# Menorah.net
KiCad netlist of a schematic drawn in EAGLE
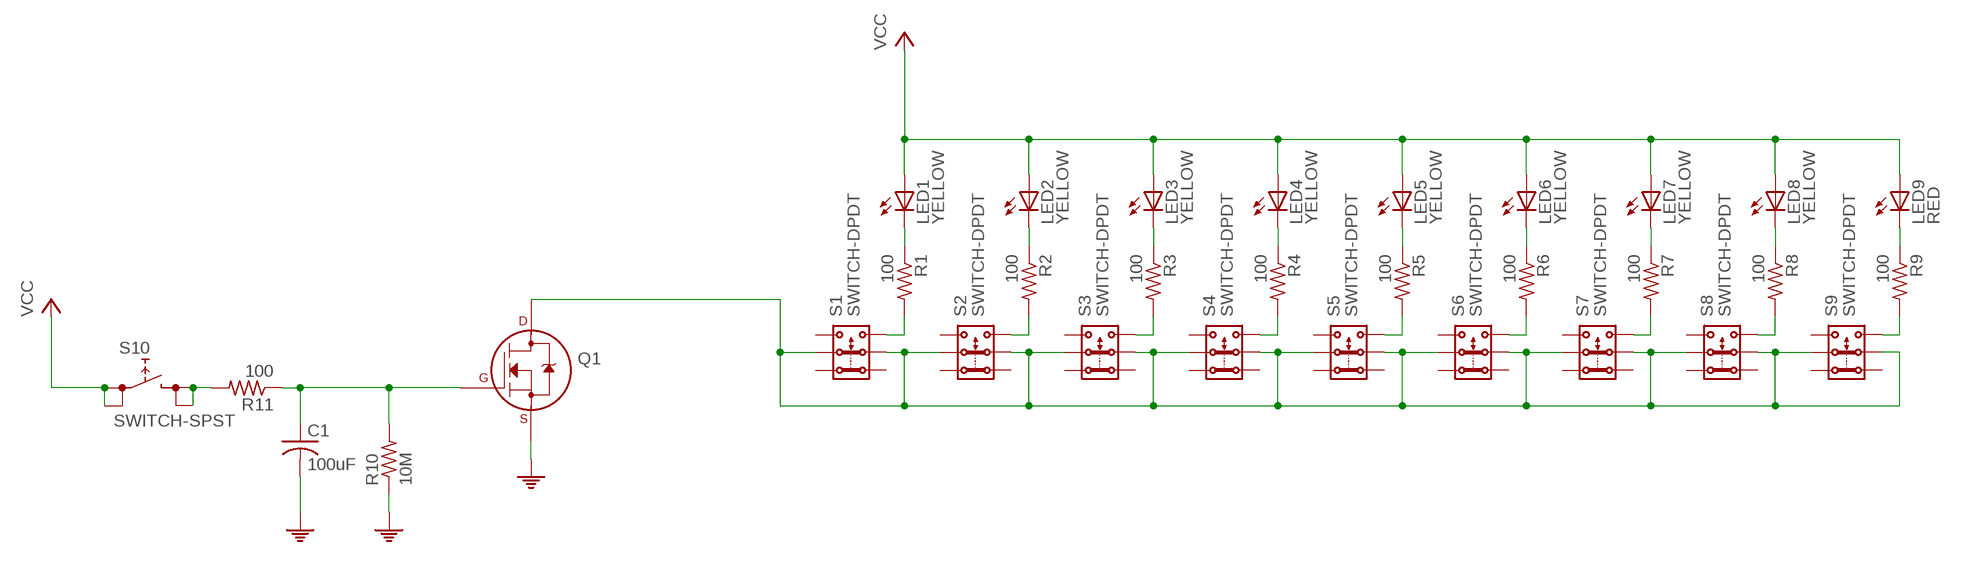
[diagram p0: schematic, sheet 1]

(export (version "E")
  (design (tool "Eeschema 10.0.6"))
  (components
    (comp (ref "C1")
      (value "100uF")
      (footprint "eagle-import:C1206")
      (libsource (lib "eagle-import") (part "C-USC1206"))
    )
    (comp (ref "LED1")
      (value "YELLOW")
      (footprint "eagle-import:CHIPLED_0805")
      (libsource (lib "eagle-import") (part "LEDCHIPLED_0805"))
    )
    (comp (ref "LED2")
      (value "YELLOW")
      (footprint "eagle-import:CHIPLED_0805")
      (libsource (lib "eagle-import") (part "LEDCHIPLED_0805"))
    )
    (comp (ref "LED3")
      (value "YELLOW")
      (footprint "eagle-import:CHIPLED_0805")
      (libsource (lib "eagle-import") (part "LEDCHIPLED_0805"))
    )
    (comp (ref "LED4")
      (value "YELLOW")
      (footprint "eagle-import:CHIPLED_0805")
      (libsource (lib "eagle-import") (part "LEDCHIPLED_0805"))
    )
    (comp (ref "LED5")
      (value "YELLOW")
      (footprint "eagle-import:CHIPLED_0805")
      (libsource (lib "eagle-import") (part "LEDCHIPLED_0805"))
    )
    (comp (ref "LED6")
      (value "YELLOW")
      (footprint "eagle-import:CHIPLED_0805")
      (libsource (lib "eagle-import") (part "LEDCHIPLED_0805"))
    )
    (comp (ref "LED7")
      (value "YELLOW")
      (footprint "eagle-import:CHIPLED_0805")
      (libsource (lib "eagle-import") (part "LEDCHIPLED_0805"))
    )
    (comp (ref "LED8")
      (value "YELLOW")
      (footprint "eagle-import:CHIPLED_0805")
      (libsource (lib "eagle-import") (part "LEDCHIPLED_0805"))
    )
    (comp (ref "LED9")
      (value "RED")
      (footprint "eagle-import:CHIPLED_0805")
      (libsource (lib "eagle-import") (part "LEDCHIPLED_0805"))
    )
    (comp (ref "Q1")
      (value "2N7002A_SOT23")
      (footprint "eagle-import:SOT-23")
      (libsource (lib "eagle-import") (part "2N700_SOT232A"))
    )
    (comp (ref "R1")
      (value "100")
      (footprint "eagle-import:R0805")
      (libsource (lib "eagle-import") (part "R-US_R0805"))
    )
    (comp (ref "R2")
      (value "100")
      (footprint "eagle-import:R0805")
      (libsource (lib "eagle-import") (part "R-US_R0805"))
    )
    (comp (ref "R3")
      (value "100")
      (footprint "eagle-import:R0805")
      (libsource (lib "eagle-import") (part "R-US_R0805"))
    )
    (comp (ref "R4")
      (value "100")
      (footprint "eagle-import:R0805")
      (libsource (lib "eagle-import") (part "R-US_R0805"))
    )
    (comp (ref "R5")
      (value "100")
      (footprint "eagle-import:R0805")
      (libsource (lib "eagle-import") (part "R-US_R0805"))
    )
    (comp (ref "R6")
      (value "100")
      (footprint "eagle-import:R0805")
      (libsource (lib "eagle-import") (part "R-US_R0805"))
    )
    (comp (ref "R7")
      (value "100")
      (footprint "eagle-import:R0805")
      (libsource (lib "eagle-import") (part "R-US_R0805"))
    )
    (comp (ref "R8")
      (value "100")
      (footprint "eagle-import:R0805")
      (libsource (lib "eagle-import") (part "R-US_R0805"))
    )
    (comp (ref "R9")
      (value "100")
      (footprint "eagle-import:R0805")
      (libsource (lib "eagle-import") (part "R-US_R0805"))
    )
    (comp (ref "R10")
      (value "10M")
      (footprint "eagle-import:R0805")
      (libsource (lib "eagle-import") (part "R-US_R0805"))
    )
    (comp (ref "R11")
      (value "100")
      (footprint "eagle-import:R0805")
      (libsource (lib "eagle-import") (part "R-US_R0805"))
    )
    (comp (ref "S1")
      (value "SWITCH-DPDT")
      (footprint "eagle-import:JS202011SCQN")
      (libsource (lib "eagle-import") (part "SWITCH-DPDT"))
    )
    (comp (ref "S2")
      (value "SWITCH-DPDT")
      (footprint "eagle-import:JS202011SCQN")
      (libsource (lib "eagle-import") (part "SWITCH-DPDT"))
    )
    (comp (ref "S3")
      (value "SWITCH-DPDT")
      (footprint "eagle-import:JS202011SCQN")
      (libsource (lib "eagle-import") (part "SWITCH-DPDT"))
    )
    (comp (ref "S4")
      (value "SWITCH-DPDT")
      (footprint "eagle-import:JS202011SCQN")
      (libsource (lib "eagle-import") (part "SWITCH-DPDT"))
    )
    (comp (ref "S5")
      (value "SWITCH-DPDT")
      (footprint "eagle-import:JS202011SCQN")
      (libsource (lib "eagle-import") (part "SWITCH-DPDT"))
    )
    (comp (ref "S6")
      (value "SWITCH-DPDT")
      (footprint "eagle-import:JS202011SCQN")
      (libsource (lib "eagle-import") (part "SWITCH-DPDT"))
    )
    (comp (ref "S7")
      (value "SWITCH-DPDT")
      (footprint "eagle-import:JS202011SCQN")
      (libsource (lib "eagle-import") (part "SWITCH-DPDT"))
    )
    (comp (ref "S8")
      (value "SWITCH-DPDT")
      (footprint "eagle-import:JS202011SCQN")
      (libsource (lib "eagle-import") (part "SWITCH-DPDT"))
    )
    (comp (ref "S9")
      (value "SWITCH-DPDT")
      (footprint "eagle-import:JS202011SCQN")
      (libsource (lib "eagle-import") (part "SWITCH-DPDT"))
    )
    (comp (ref "S10")
      (value "SWITCH-SPST")
      (footprint "eagle-import:KS-01Q-01")
      (libsource (lib "eagle-import") (part "SWITCH-SPST"))
    )
  )
  (nets
    (net (code "1") (name "Net-(LED1-PadC)") (class "Default")
      (node (ref "LED1") (pin "C") (pinfunction "C_C") (pintype "passive"))
      (node (ref "R1") (pin "1") (pinfunction "1_1") (pintype "passive"))
    )
    (net (code "2") (name "Net-(LED2-PadC)") (class "Default")
      (node (ref "LED2") (pin "C") (pinfunction "C_C") (pintype "passive"))
      (node (ref "R2") (pin "1") (pinfunction "1_1") (pintype "passive"))
    )
    (net (code "3") (name "Net-(LED3-PadC)") (class "Default")
      (node (ref "LED3") (pin "C") (pinfunction "C_C") (pintype "passive"))
      (node (ref "R3") (pin "1") (pinfunction "1_1") (pintype "passive"))
    )
    (net (code "4") (name "Net-(LED4-PadC)") (class "Default")
      (node (ref "LED4") (pin "C") (pinfunction "C_C") (pintype "passive"))
      (node (ref "R4") (pin "1") (pinfunction "1_1") (pintype "passive"))
    )
    (net (code "5") (name "Net-(LED5-PadC)") (class "Default")
      (node (ref "LED5") (pin "C") (pinfunction "C_C") (pintype "passive"))
      (node (ref "R5") (pin "1") (pinfunction "1_1") (pintype "passive"))
    )
    (net (code "6") (name "Net-(LED6-PadC)") (class "Default")
      (node (ref "LED6") (pin "C") (pinfunction "C_C") (pintype "passive"))
      (node (ref "R6") (pin "1") (pinfunction "1_1") (pintype "passive"))
    )
    (net (code "7") (name "Net-(LED7-PadC)") (class "Default")
      (node (ref "LED7") (pin "C") (pinfunction "C_C") (pintype "passive"))
      (node (ref "R7") (pin "1") (pinfunction "1_1") (pintype "passive"))
    )
    (net (code "8") (name "Net-(LED8-PadC)") (class "Default")
      (node (ref "LED8") (pin "C") (pinfunction "C_C") (pintype "passive"))
      (node (ref "R8") (pin "1") (pinfunction "1_1") (pintype "passive"))
    )
    (net (code "9") (name "Net-(LED9-PadC)") (class "Default")
      (node (ref "LED9") (pin "C") (pinfunction "C_C") (pintype "passive"))
      (node (ref "R9") (pin "1") (pinfunction "1_1") (pintype "passive"))
    )
    (net (code "10") (name "Net-(Q1-D)") (class "Default")
      (node (ref "Q1") (pin "3") (pinfunction "D_3") (pintype "bidirectional"))
      (node (ref "S1") (pin "2") (pinfunction "2_2") (pintype "passive"))
      (node (ref "S1") (pin "5") (pinfunction "5_5") (pintype "passive"))
      (node (ref "S2") (pin "2") (pinfunction "2_2") (pintype "passive"))
      (node (ref "S2") (pin "5") (pinfunction "5_5") (pintype "passive"))
      (node (ref "S3") (pin "2") (pinfunction "2_2") (pintype "passive"))
      (node (ref "S3") (pin "5") (pinfunction "5_5") (pintype "passive"))
      (node (ref "S4") (pin "2") (pinfunction "2_2") (pintype "passive"))
      (node (ref "S4") (pin "5") (pinfunction "5_5") (pintype "passive"))
      (node (ref "S5") (pin "2") (pinfunction "2_2") (pintype "passive"))
      (node (ref "S5") (pin "5") (pinfunction "5_5") (pintype "passive"))
      (node (ref "S6") (pin "2") (pinfunction "2_2") (pintype "passive"))
      (node (ref "S6") (pin "5") (pinfunction "5_5") (pintype "passive"))
      (node (ref "S7") (pin "2") (pinfunction "2_2") (pintype "passive"))
      (node (ref "S7") (pin "5") (pinfunction "5_5") (pintype "passive"))
      (node (ref "S8") (pin "2") (pinfunction "2_2") (pintype "passive"))
      (node (ref "S8") (pin "5") (pinfunction "5_5") (pintype "passive"))
      (node (ref "S9") (pin "2") (pinfunction "2_2") (pintype "passive"))
      (node (ref "S9") (pin "5") (pinfunction "5_5") (pintype "passive"))
    )
    (net (code "11") (name "Net-(Q1-G)") (class "Default")
      (node (ref "C1") (pin "1") (pinfunction "1_1") (pintype "passive"))
      (node (ref "Q1") (pin "1") (pinfunction "G_1") (pintype "tri_state"))
      (node (ref "R10") (pin "2") (pinfunction "2_2") (pintype "passive"))
      (node (ref "R11") (pin "1") (pinfunction "1_1") (pintype "passive"))
    )
    (net (code "12") (name "Net-(R1-Pad2)") (class "Default")
      (node (ref "R1") (pin "2") (pinfunction "2_2") (pintype "passive"))
      (node (ref "S1") (pin "3") (pinfunction "3_3") (pintype "passive"))
    )
    (net (code "13") (name "Net-(R2-Pad2)") (class "Default")
      (node (ref "R2") (pin "2") (pinfunction "2_2") (pintype "passive"))
      (node (ref "S2") (pin "3") (pinfunction "3_3") (pintype "passive"))
    )
    (net (code "14") (name "Net-(R3-Pad2)") (class "Default")
      (node (ref "R3") (pin "2") (pinfunction "2_2") (pintype "passive"))
      (node (ref "S3") (pin "3") (pinfunction "3_3") (pintype "passive"))
    )
    (net (code "15") (name "Net-(R4-Pad2)") (class "Default")
      (node (ref "R4") (pin "2") (pinfunction "2_2") (pintype "passive"))
      (node (ref "S4") (pin "3") (pinfunction "3_3") (pintype "passive"))
    )
    (net (code "16") (name "Net-(R5-Pad2)") (class "Default")
      (node (ref "R5") (pin "2") (pinfunction "2_2") (pintype "passive"))
      (node (ref "S5") (pin "3") (pinfunction "3_3") (pintype "passive"))
    )
    (net (code "17") (name "Net-(R6-Pad2)") (class "Default")
      (node (ref "R6") (pin "2") (pinfunction "2_2") (pintype "passive"))
      (node (ref "S6") (pin "3") (pinfunction "3_3") (pintype "passive"))
    )
    (net (code "18") (name "Net-(R7-Pad2)") (class "Default")
      (node (ref "R7") (pin "2") (pinfunction "2_2") (pintype "passive"))
      (node (ref "S7") (pin "3") (pinfunction "3_3") (pintype "passive"))
    )
    (net (code "19") (name "Net-(R8-Pad2)") (class "Default")
      (node (ref "R8") (pin "2") (pinfunction "2_2") (pintype "passive"))
      (node (ref "S8") (pin "3") (pinfunction "3_3") (pintype "passive"))
    )
    (net (code "20") (name "Net-(R9-Pad2)") (class "Default")
      (node (ref "R9") (pin "2") (pinfunction "2_2") (pintype "passive"))
      (node (ref "S9") (pin "3") (pinfunction "3_3") (pintype "passive"))
    )
    (net (code "21") (name "Net-(R11-Pad2)") (class "Default")
      (node (ref "R11") (pin "2") (pinfunction "2_2") (pintype "passive"))
      (node (ref "S10") (pin "2") (pinfunction "1_2") (pintype "passive"))
      (node (ref "S10") (pin "4") (pinfunction "1_4") (pintype "passive"))
    )
    (net (code "22") (name "PE") (class "Default")
      (node (ref "C1") (pin "2") (pinfunction "2_2") (pintype "passive"))
      (node (ref "Q1") (pin "2") (pinfunction "S_2") (pintype "bidirectional"))
      (node (ref "R10") (pin "1") (pinfunction "1_1") (pintype "passive"))
    )
    (net (code "23") (name "VCC") (class "Default")
      (node (ref "LED1") (pin "A") (pinfunction "A_A") (pintype "passive"))
      (node (ref "LED2") (pin "A") (pinfunction "A_A") (pintype "passive"))
      (node (ref "LED3") (pin "A") (pinfunction "A_A") (pintype "passive"))
      (node (ref "LED4") (pin "A") (pinfunction "A_A") (pintype "passive"))
      (node (ref "LED5") (pin "A") (pinfunction "A_A") (pintype "passive"))
      (node (ref "LED6") (pin "A") (pinfunction "A_A") (pintype "passive"))
      (node (ref "LED7") (pin "A") (pinfunction "A_A") (pintype "passive"))
      (node (ref "LED8") (pin "A") (pinfunction "A_A") (pintype "passive"))
      (node (ref "LED9") (pin "A") (pinfunction "A_A") (pintype "passive"))
      (node (ref "S10") (pin "1") (pinfunction "0_1") (pintype "passive"))
      (node (ref "S10") (pin "3") (pinfunction "0_3") (pintype "passive"))
    )
    (net (code "24") (name "unconnected-(S1-Pad1)") (class "Default")
      (node (ref "S1") (pin "1") (pinfunction "1_1") (pintype "passive"))
    )
    (net (code "25") (name "unconnected-(S1-Pad4)") (class "Default")
      (node (ref "S1") (pin "4") (pinfunction "4_4") (pintype "passive"))
    )
    (net (code "26") (name "unconnected-(S1-Pad6)") (class "Default")
      (node (ref "S1") (pin "6") (pinfunction "6_6") (pintype "passive"))
    )
    (net (code "27") (name "unconnected-(S2-Pad1)") (class "Default")
      (node (ref "S2") (pin "1") (pinfunction "1_1") (pintype "passive"))
    )
    (net (code "28") (name "unconnected-(S2-Pad4)") (class "Default")
      (node (ref "S2") (pin "4") (pinfunction "4_4") (pintype "passive"))
    )
    (net (code "29") (name "unconnected-(S2-Pad6)") (class "Default")
      (node (ref "S2") (pin "6") (pinfunction "6_6") (pintype "passive"))
    )
    (net (code "30") (name "unconnected-(S3-Pad1)") (class "Default")
      (node (ref "S3") (pin "1") (pinfunction "1_1") (pintype "passive"))
    )
    (net (code "31") (name "unconnected-(S3-Pad4)") (class "Default")
      (node (ref "S3") (pin "4") (pinfunction "4_4") (pintype "passive"))
    )
    (net (code "32") (name "unconnected-(S3-Pad6)") (class "Default")
      (node (ref "S3") (pin "6") (pinfunction "6_6") (pintype "passive"))
    )
    (net (code "33") (name "unconnected-(S4-Pad1)") (class "Default")
      (node (ref "S4") (pin "1") (pinfunction "1_1") (pintype "passive"))
    )
    (net (code "34") (name "unconnected-(S4-Pad4)") (class "Default")
      (node (ref "S4") (pin "4") (pinfunction "4_4") (pintype "passive"))
    )
    (net (code "35") (name "unconnected-(S4-Pad6)") (class "Default")
      (node (ref "S4") (pin "6") (pinfunction "6_6") (pintype "passive"))
    )
    (net (code "36") (name "unconnected-(S5-Pad1)") (class "Default")
      (node (ref "S5") (pin "1") (pinfunction "1_1") (pintype "passive"))
    )
    (net (code "37") (name "unconnected-(S5-Pad4)") (class "Default")
      (node (ref "S5") (pin "4") (pinfunction "4_4") (pintype "passive"))
    )
    (net (code "38") (name "unconnected-(S5-Pad6)") (class "Default")
      (node (ref "S5") (pin "6") (pinfunction "6_6") (pintype "passive"))
    )
    (net (code "39") (name "unconnected-(S6-Pad1)") (class "Default")
      (node (ref "S6") (pin "1") (pinfunction "1_1") (pintype "passive"))
    )
    (net (code "40") (name "unconnected-(S6-Pad4)") (class "Default")
      (node (ref "S6") (pin "4") (pinfunction "4_4") (pintype "passive"))
    )
    (net (code "41") (name "unconnected-(S6-Pad6)") (class "Default")
      (node (ref "S6") (pin "6") (pinfunction "6_6") (pintype "passive"))
    )
    (net (code "42") (name "unconnected-(S7-Pad1)") (class "Default")
      (node (ref "S7") (pin "1") (pinfunction "1_1") (pintype "passive"))
    )
    (net (code "43") (name "unconnected-(S7-Pad4)") (class "Default")
      (node (ref "S7") (pin "4") (pinfunction "4_4") (pintype "passive"))
    )
    (net (code "44") (name "unconnected-(S7-Pad6)") (class "Default")
      (node (ref "S7") (pin "6") (pinfunction "6_6") (pintype "passive"))
    )
    (net (code "45") (name "unconnected-(S8-Pad1)") (class "Default")
      (node (ref "S8") (pin "1") (pinfunction "1_1") (pintype "passive"))
    )
    (net (code "46") (name "unconnected-(S8-Pad4)") (class "Default")
      (node (ref "S8") (pin "4") (pinfunction "4_4") (pintype "passive"))
    )
    (net (code "47") (name "unconnected-(S8-Pad6)") (class "Default")
      (node (ref "S8") (pin "6") (pinfunction "6_6") (pintype "passive"))
    )
    (net (code "48") (name "unconnected-(S9-Pad1)") (class "Default")
      (node (ref "S9") (pin "1") (pinfunction "1_1") (pintype "passive"))
    )
    (net (code "49") (name "unconnected-(S9-Pad4)") (class "Default")
      (node (ref "S9") (pin "4") (pinfunction "4_4") (pintype "passive"))
    )
    (net (code "50") (name "unconnected-(S9-Pad6)") (class "Default")
      (node (ref "S9") (pin "6") (pinfunction "6_6") (pintype "passive"))
    )
  )
)
